# BUTTON_LED.net
KiCad netlist of a schematic drawn in Altium Designer
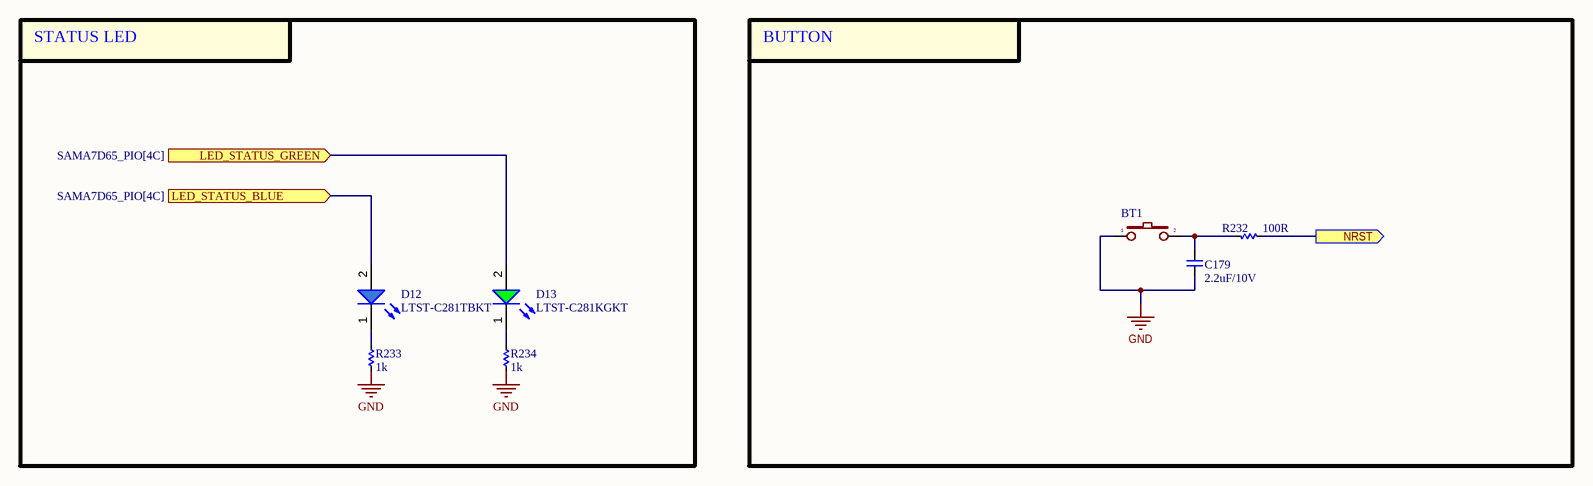
[diagram p0: BUTTON_LED.SchDoc]

(export (version "E")
  (design (tool "Eeschema 10.0.6"))
  (components
    (comp (ref "BT1")
      (value "BT_")
      (footprint "SW2-SMD")
      (description "Switch button 2 pin")
      (libsource (lib "IFBschelib") (part "BT2"))
    )
    (comp (ref "C179")
      (value "2.2uF/10V")
      (footprint "CAP_C_1005X50_L")
      (description "CAP CHIP")
      (libsource (lib "IFBschelib") (part "_CAP_C_2"))
    )
    (comp (ref "D12")
      (value "LTST-C281TBKT")
      (footprint "LED_0402")
      (libsource (lib "IFBschelib") (part "LED_BLUE"))
    )
    (comp (ref "D13")
      (value "LTST-C281KGKT")
      (footprint "LED_0402")
      (description "LED GREEN CLEAR 0402 SMD")
      (libsource (lib "IFBschelib") (part "LED_GREEN"))
    )
    (comp (ref "R232")
      (value "100R")
      (footprint "RES_C_1005x30_L")
      (description "RES")
      (libsource (lib "IFBschelib") (part "_RES_B_2"))
    )
    (comp (ref "R233")
      (value "1k")
      (footprint "RES_C_1005x30_L")
      (description "RES")
      (libsource (lib "IFBschelib") (part "_RES_B_2"))
    )
    (comp (ref "R234")
      (value "1k")
      (footprint "RES_C_1005x30_L")
      (description "RES")
      (libsource (lib "IFBschelib") (part "_RES_B_2"))
    )
  )
  (nets
    (net (code "1") (name "/LED_STATUS_BLUE") (class "Default")
      (node (ref "D12") (pin "2") (pinfunction "A_2") (pintype "passive"))
    )
    (net (code "2") (name "/LED_STATUS_GREEN") (class "Default")
      (node (ref "D13") (pin "2") (pinfunction "A_2") (pintype "passive"))
    )
    (net (code "3") (name "/NRST") (class "Default")
      (node (ref "R232") (pin "2") (pinfunction "2_2") (pintype "passive"))
    )
    (net (code "4") (name "GND") (class "Default")
      (node (ref "BT1") (pin "1") (pinfunction "1_1") (pintype "passive"))
      (node (ref "C179") (pin "1") (pinfunction "1_1") (pintype "passive"))
      (node (ref "R233") (pin "1") (pinfunction "1_1") (pintype "passive"))
      (node (ref "R234") (pin "1") (pinfunction "1_1") (pintype "passive"))
    )
    (net (code "5") (name "Net-(BT1-Pad2)") (class "Default")
      (node (ref "BT1") (pin "2") (pinfunction "2_2") (pintype "passive"))
      (node (ref "C179") (pin "2") (pinfunction "2_2") (pintype "passive"))
      (node (ref "R232") (pin "1") (pinfunction "1_1") (pintype "passive"))
    )
    (net (code "6") (name "Net-(D12-K)") (class "Default")
      (node (ref "D12") (pin "1") (pinfunction "K_1") (pintype "passive"))
      (node (ref "R233") (pin "2") (pinfunction "2_2") (pintype "passive"))
    )
    (net (code "7") (name "Net-(D13-K)") (class "Default")
      (node (ref "D13") (pin "1") (pinfunction "K_1") (pintype "passive"))
      (node (ref "R234") (pin "2") (pinfunction "2_2") (pintype "passive"))
    )
  )
)
